# AdelinoR2B.net
KiCad netlist of a schematic drawn in EAGLE
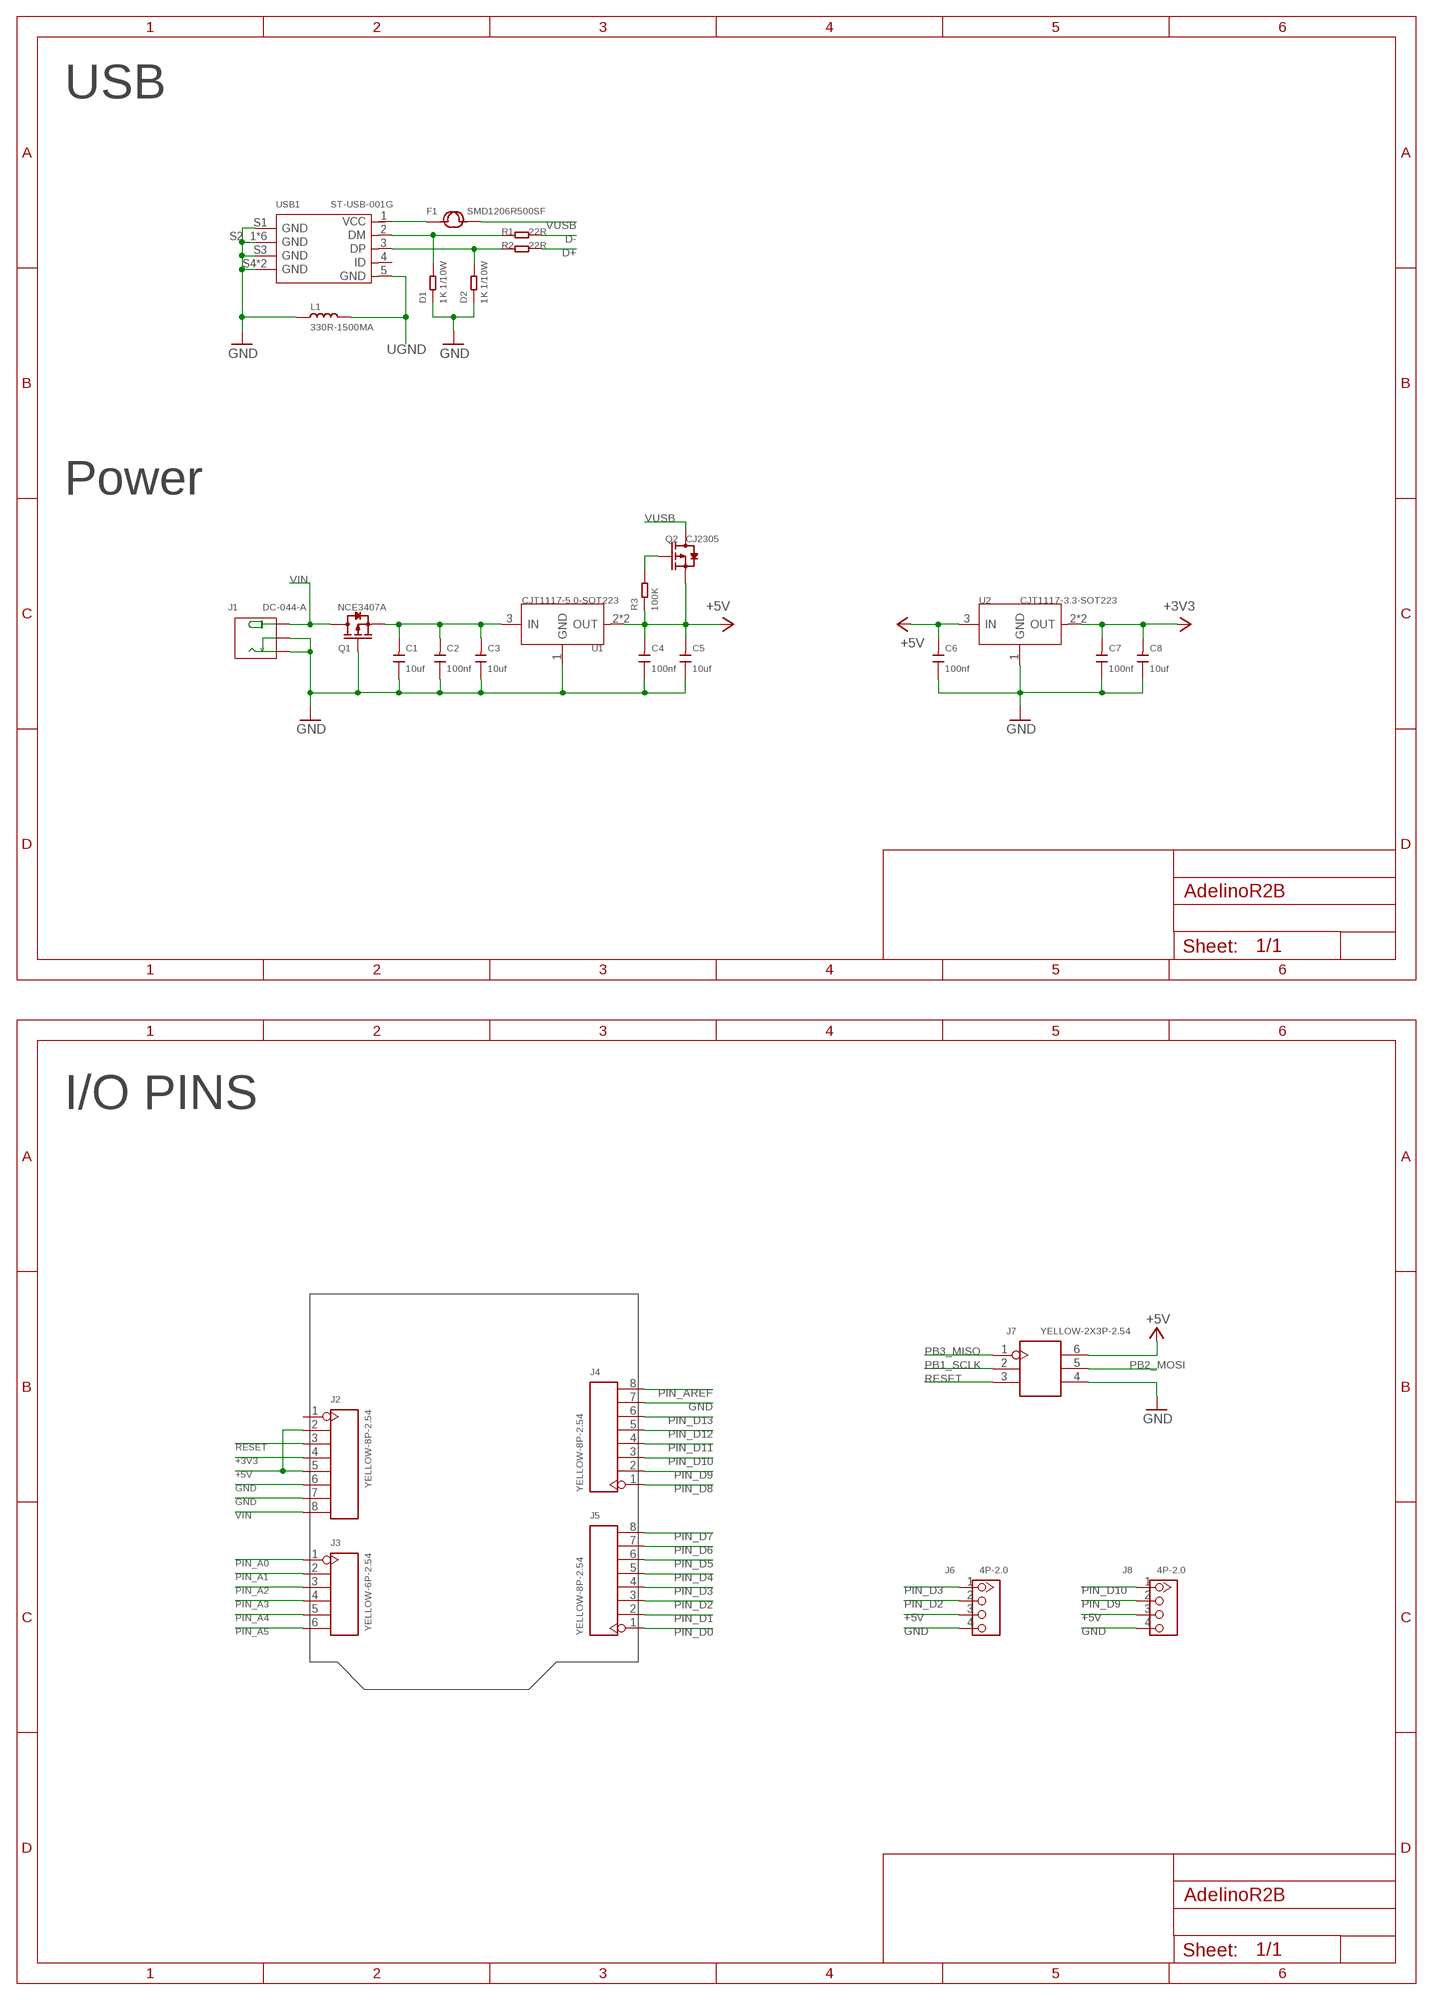
[diagram p0: schematic, sheet 1, part 1 of 2]
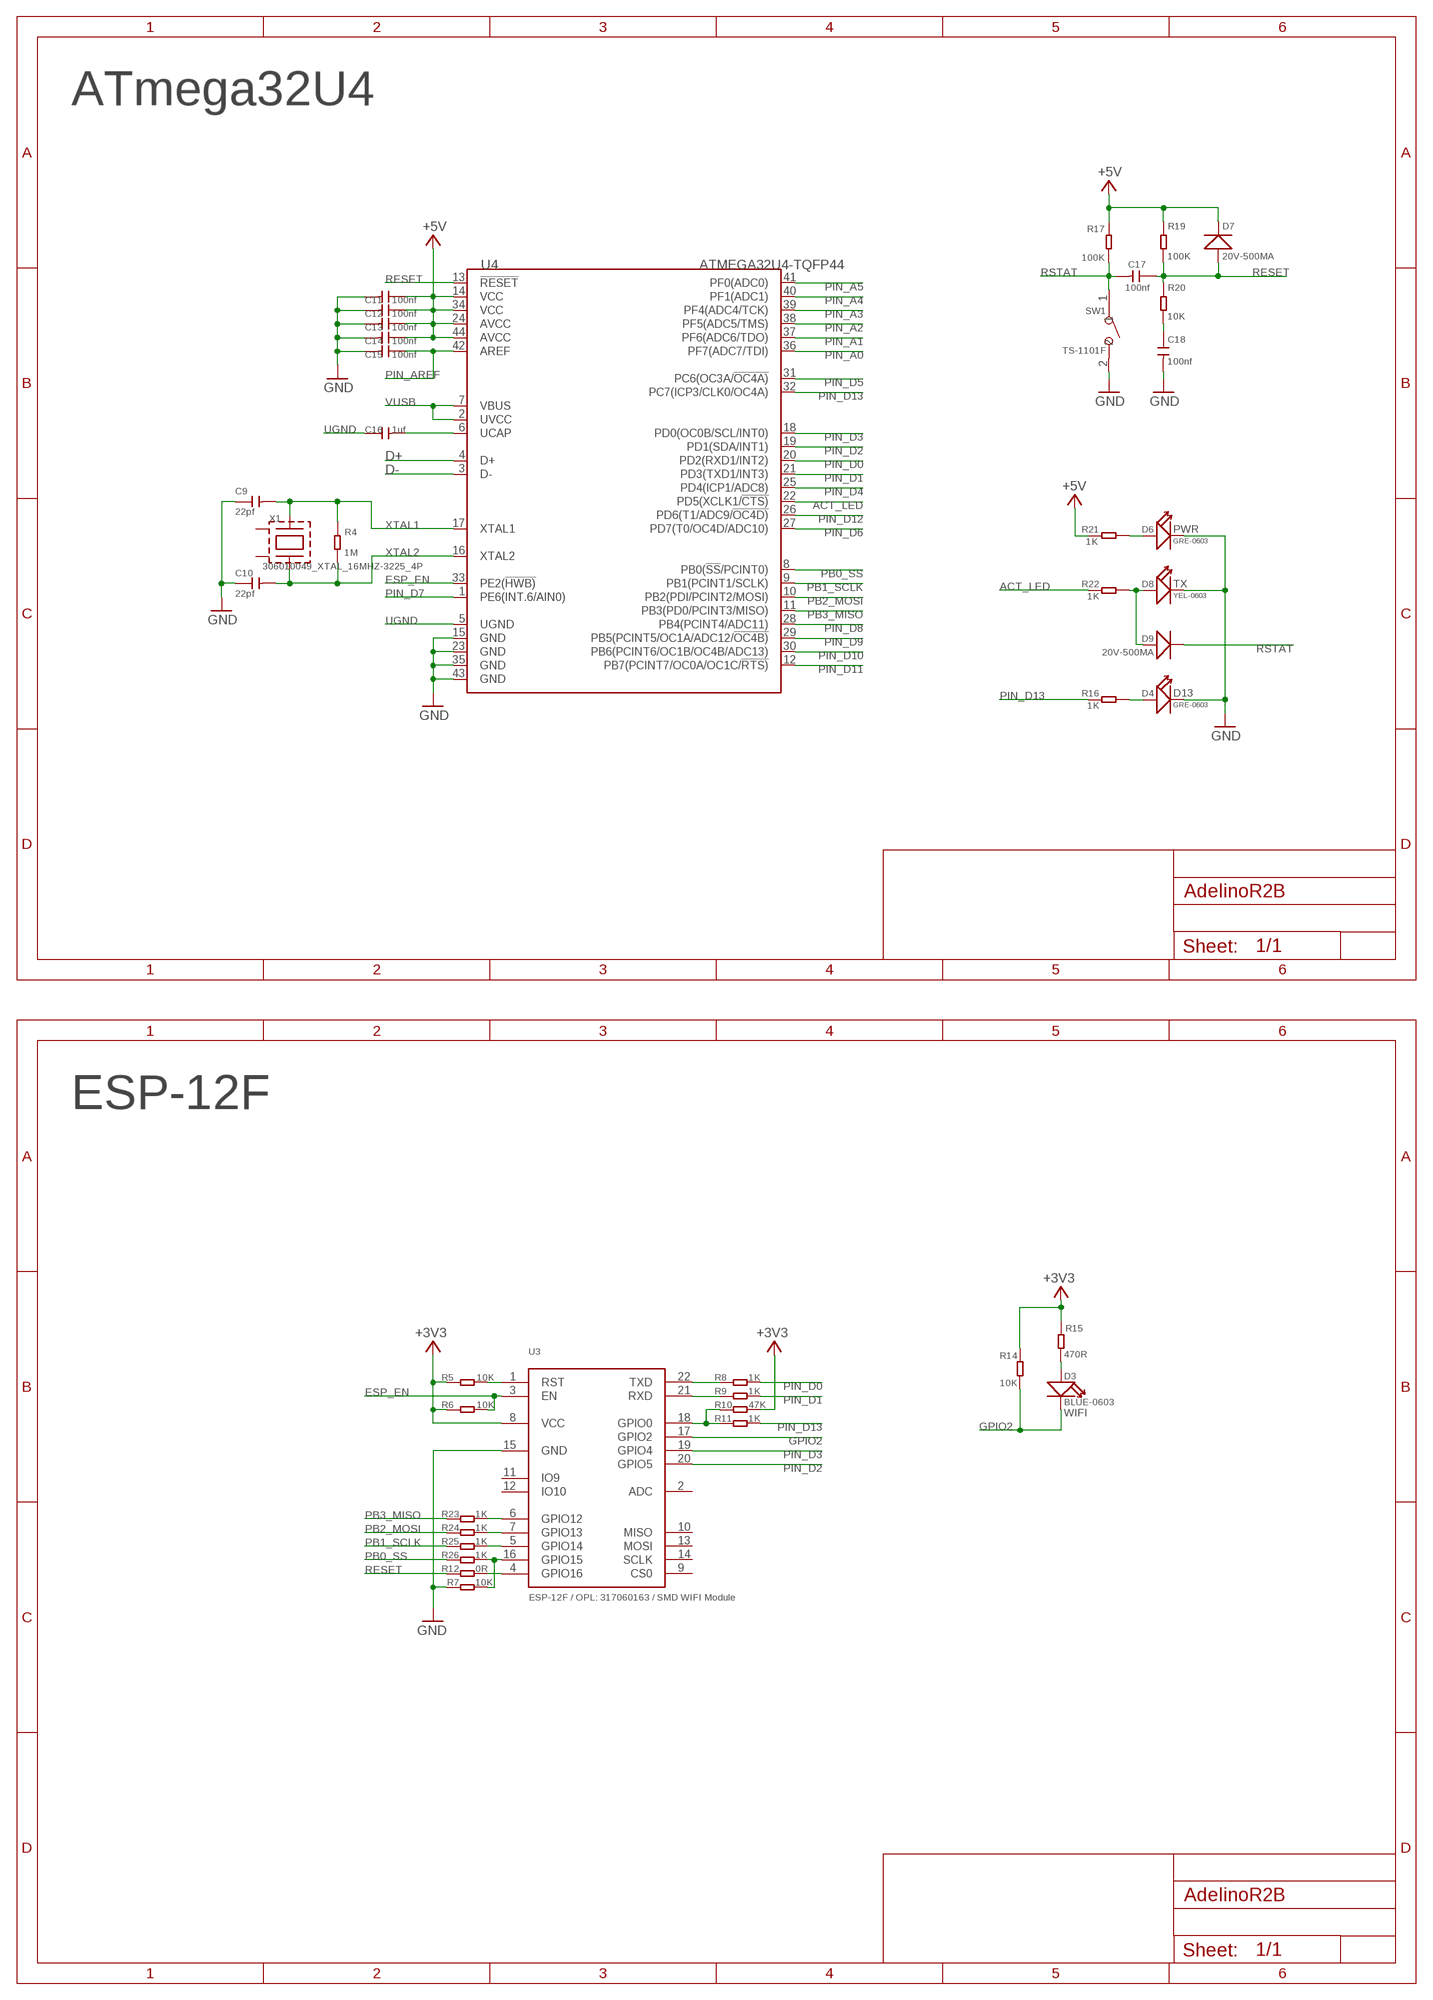
[diagram p1: schematic, sheet 1, part 2 of 2]

(export (version "E")
  (design (tool "Eeschema 10.0.6"))
  (components
    (comp (ref "C1")
      (value "10uf")
      (footprint "eagle-import:C0805")
      (fields (field (name "MPN") "CC0805KKX5R8BB106"))
      (libsource (lib "eagle-import") (part "CERAMIC-10UF-25V-10%-X5R(0805)"))
    )
    (comp (ref "C2")
      (value "100nf")
      (footprint "eagle-import:C0402")
      (fields (field (name "MPN") "CC0402KRX7R8BB104"))
      (libsource (lib "eagle-import") (part "CERAMIC-100NF-25V-10%-X7R(0402)"))
    )
    (comp (ref "C3")
      (value "10uf")
      (footprint "eagle-import:C0805")
      (fields (field (name "MPN") "CC0805KKX5R8BB106"))
      (libsource (lib "eagle-import") (part "CERAMIC-10UF-25V-10%-X5R(0805)"))
    )
    (comp (ref "C4")
      (value "100nf")
      (footprint "eagle-import:C0402")
      (fields (field (name "MPN") "CC0402KRX7R8BB104"))
      (libsource (lib "eagle-import") (part "CERAMIC-100NF-25V-10%-X7R(0402)"))
    )
    (comp (ref "C5")
      (value "10uf")
      (footprint "eagle-import:C0805")
      (fields (field (name "MPN") "CC0805KKX5R8BB106"))
      (libsource (lib "eagle-import") (part "CERAMIC-10UF-25V-10%-X5R(0805)"))
    )
    (comp (ref "C6")
      (value "100nf")
      (footprint "eagle-import:C0402")
      (fields (field (name "MPN") "CC0402KRX7R8BB104"))
      (libsource (lib "eagle-import") (part "CERAMIC-100NF-25V-10%-X7R(0402)"))
    )
    (comp (ref "C7")
      (value "100nf")
      (footprint "eagle-import:C0402")
      (fields (field (name "MPN") "CC0402KRX7R8BB104"))
      (libsource (lib "eagle-import") (part "CERAMIC-100NF-25V-10%-X7R(0402)"))
    )
    (comp (ref "C8")
      (value "10uf")
      (footprint "eagle-import:C0805")
      (fields (field (name "MPN") "CC0805KKX5R8BB106"))
      (libsource (lib "eagle-import") (part "CERAMIC-10UF-25V-10%-X5R(0805)"))
    )
    (comp (ref "C9")
      (value "22pf")
      (footprint "eagle-import:C0402")
      (fields (field (name "MPN") "CC0402JRNPO9BN220"))
      (libsource (lib "eagle-import") (part "CERAMIC-22PF-50V-5%-NPO(0402)"))
    )
    (comp (ref "C10")
      (value "22pf")
      (footprint "eagle-import:C0402")
      (fields (field (name "MPN") "CC0402JRNPO9BN220"))
      (libsource (lib "eagle-import") (part "CERAMIC-22PF-50V-5%-NPO(0402)"))
    )
    (comp (ref "C11")
      (value "100nf")
      (footprint "eagle-import:C0402")
      (fields (field (name "MPN") "CC0402KRX7R8BB104"))
      (libsource (lib "eagle-import") (part "CERAMIC-100NF-25V-10%-X7R(0402)"))
    )
    (comp (ref "C12")
      (value "100nf")
      (footprint "eagle-import:C0402")
      (fields (field (name "MPN") "CC0402KRX7R8BB104"))
      (libsource (lib "eagle-import") (part "CERAMIC-100NF-25V-10%-X7R(0402)"))
    )
    (comp (ref "C13")
      (value "100nf")
      (footprint "eagle-import:C0402")
      (fields (field (name "MPN") "CC0402KRX7R8BB104"))
      (libsource (lib "eagle-import") (part "CERAMIC-100NF-25V-10%-X7R(0402)"))
    )
    (comp (ref "C14")
      (value "100nf")
      (footprint "eagle-import:C0402")
      (fields (field (name "MPN") "CC0402KRX7R8BB104"))
      (libsource (lib "eagle-import") (part "CERAMIC-100NF-25V-10%-X7R(0402)"))
    )
    (comp (ref "C15")
      (value "100nf")
      (footprint "eagle-import:C0402")
      (fields (field (name "MPN") "CC0402KRX7R8BB104"))
      (libsource (lib "eagle-import") (part "CERAMIC-100NF-25V-10%-X7R(0402)"))
    )
    (comp (ref "C16")
      (value "1uf")
      (footprint "eagle-import:C0805")
      (fields (field (name "MPN") "CC0805KKX7R8BB105"))
      (libsource (lib "eagle-import") (part "CERAMIC-1UF-25V-10%-X7R(0805)"))
    )
    (comp (ref "C17")
      (value "100nf")
      (footprint "eagle-import:C0402")
      (fields (field (name "MPN") "CC0402KRX7R8BB104"))
      (libsource (lib "eagle-import") (part "CERAMIC-100NF-25V-10%-X7R(0402)"))
    )
    (comp (ref "C18")
      (value "100nf")
      (footprint "eagle-import:C0402")
      (fields (field (name "MPN") "CC0402KRX7R8BB104"))
      (libsource (lib "eagle-import") (part "CERAMIC-100NF-25V-10%-X7R(0402)"))
    )
    (comp (ref "D1")
      (value "1K 1/10W")
      (footprint "eagle-import:D0603")
      (fields (field (name "MPN") "RC0603JR-071KL"))
      (libsource (lib "eagle-import") (part "SMD-ESD-CG0603MLC-05E"))
    )
    (comp (ref "D2")
      (value "1K 1/10W")
      (footprint "eagle-import:D0603")
      (fields (field (name "MPN") "RC0603JR-071KL"))
      (libsource (lib "eagle-import") (part "SMD-ESD-CG0603MLC-05E"))
    )
    (comp (ref "D3")
      (value "BLUE-0603")
      (footprint "eagle-import:LED-0603")
      (fields (field (name "MPN") "19-217-BHC-ZL1M2RY-3T") (field (name "LABEL") "WIFI"))
      (libsource (lib "eagle-import") (part "SMD-LED-CLEAR-BLUE(0603)"))
    )
    (comp (ref "D4")
      (value "GRE-0603")
      (footprint "eagle-import:LED-0603")
      (fields (field (name "MPN") "19-217-G7C-AN1P2-3T") (field (name "LABEL") "D13"))
      (libsource (lib "eagle-import") (part "SMD-LED-CLEAR-GREEN(0603)"))
    )
    (comp (ref "D6")
      (value "GRE-0603")
      (footprint "eagle-import:LED-0603")
      (fields (field (name "MPN") "19-217-G7C-AN1P2-3T") (field (name "LABEL") "PWR"))
      (libsource (lib "eagle-import") (part "SMD-LED-CLEAR-GREEN(0603)"))
    )
    (comp (ref "D7")
      (value "20V-500MA")
      (footprint "eagle-import:SOD-123")
      (fields (field (name "MPN") "MBR0520LT1G"))
      (libsource (lib "eagle-import") (part "SMD-DIODE-SCHOTTKY-20V-500MA(SOD-123)P"))
    )
    (comp (ref "D8")
      (value "YEL-0603")
      (footprint "eagle-import:LED-0603")
      (fields (field (name "MPN") "19-217-Y5C-AM1N1VY-3T") (field (name "LABEL") "TX"))
      (libsource (lib "eagle-import") (part "SMD-LED-CLEAR-YELLOW(0603)"))
    )
    (comp (ref "D9")
      (value "20V-500MA")
      (footprint "eagle-import:SOD-123")
      (fields (field (name "MPN") "MBR0520LT1G"))
      (libsource (lib "eagle-import") (part "SMD-DIODE-SCHOTTKY-20V-500MA(SOD-123)P"))
    )
    (comp (ref "F1")
      (value "SMD1206R500SF")
      (footprint "eagle-import:F1206")
      (libsource (lib "eagle-import") (part "SMD-PPTC-500MA(1206)"))
    )
    (comp (ref "J1")
      (value "DC-044-A")
      (footprint "eagle-import:DCJ3P-11.6X9.6X7.0MM")
      (fields (field (name "MPN") "JACK-DC-044-A"))
      (libsource (lib "eagle-import") (part "JACK-DC-044-A"))
    )
    (comp (ref "J2")
      (value "YELLOW-8P-2.54")
      (footprint "eagle-import:H8-2.54")
      (fields (field (name "MPN") "F185-1108A1BSYC1"))
      (libsource (lib "eagle-import") (part "DIP-YELLOW-FEMALE-HEADER(8P-2.54)"))
    )
    (comp (ref "J3")
      (value "YELLOW-6P-2.54")
      (footprint "eagle-import:H6-2.54")
      (fields (field (name "MPN") "F185-1106A1BSYA3"))
      (libsource (lib "eagle-import") (part "DIP-YELLOW-FEMALE-HEADER-VERT(6P-2.54)"))
    )
    (comp (ref "J4")
      (value "YELLOW-8P-2.54")
      (footprint "eagle-import:H8-2.54")
      (fields (field (name "MPN") "F185-1108A1BSYC1"))
      (libsource (lib "eagle-import") (part "DIP-YELLOW-FEMALE-HEADER(8P-2.54)"))
    )
    (comp (ref "J5")
      (value "YELLOW-8P-2.54")
      (footprint "eagle-import:H8-2.54")
      (fields (field (name "MPN") "F185-1108A1BSYC1"))
      (libsource (lib "eagle-import") (part "DIP-YELLOW-FEMALE-HEADER(8P-2.54)"))
    )
    (comp (ref "J6")
      (value "4P-2.0")
      (footprint "eagle-import:HW4-2.0")
      (libsource (lib "eagle-import") (part "GROVE-CONNECTOR-DIP(4P-2.0)"))
    )
    (comp (ref "J7")
      (value "YELLOW-2X3P-2.54")
      (footprint "eagle-import:H2X3-2.54")
      (fields (field (name "MPN") "P125-1203A0BS116A2"))
      (libsource (lib "eagle-import") (part "DIP-YELLOW-MALE-HEADER-VERT(2X3P-2.54)"))
    )
    (comp (ref "J8")
      (value "4P-2.0")
      (footprint "eagle-import:HW4-2.0")
      (libsource (lib "eagle-import") (part "GROVE-CONNECTOR-DIP(4P-2.0)"))
    )
    (comp (ref "L1")
      (value "330R-1500MA")
      (footprint "eagle-import:L0805")
      (fields (field (name "MPN") "BLM21PG331SN1D"))
      (libsource (lib "eagle-import") (part "SMD-FERRITE-BEAD-330R-1500MA(0805)'0805'"))
    )
    (comp (ref "Q1")
      (value "NCE3407A")
      (footprint "eagle-import:SOT-23")
      (libsource (lib "eagle-import") (part "SMD-MOSFET-P-CH-VDC=30V-ID=4.3A-NCE3407A(SOT-23)"))
    )
    (comp (ref "Q2")
      (value "CJ2305")
      (footprint "eagle-import:SOT-23")
      (libsource (lib "eagle-import") (part "SMD-MOSFET-P-CH-8V-4.1A-CJ2305(SOT-23)"))
    )
    (comp (ref "R1")
      (value "22R")
      (footprint "eagle-import:R0402")
      (fields (field (name "MPN") "RC0402FR-0722RL"))
      (libsource (lib "eagle-import") (part "SMD-RES-22R-1%-1/16W(0402)"))
    )
    (comp (ref "R2")
      (value "22R")
      (footprint "eagle-import:R0402")
      (fields (field (name "MPN") "RC0402FR-0722RL"))
      (libsource (lib "eagle-import") (part "SMD-RES-22R-1%-1/16W(0402)"))
    )
    (comp (ref "R3")
      (value "100K")
      (footprint "eagle-import:R0402")
      (fields (field (name "MPN") "RC0402FR-07100KL"))
      (libsource (lib "eagle-import") (part "SMD-RES-100K-1%-1/16W(0402)"))
    )
    (comp (ref "R4")
      (value "1M")
      (footprint "eagle-import:R0402")
      (fields (field (name "MPN") "RC0402FR-071ML"))
      (libsource (lib "eagle-import") (part "SMD-RES-1M-1%-1/16W(0402)"))
    )
    (comp (ref "R5")
      (value "10K")
      (footprint "eagle-import:R0402")
      (fields (field (name "MPN") "RC0402FR-0710KL"))
      (libsource (lib "eagle-import") (part "SMD-RES-10K-1%-1/16W(0402)"))
    )
    (comp (ref "R6")
      (value "10K")
      (footprint "eagle-import:R0402")
      (fields (field (name "MPN") "RC0402FR-0710KL"))
      (libsource (lib "eagle-import") (part "SMD-RES-10K-1%-1/16W(0402)"))
    )
    (comp (ref "R7")
      (value "10K")
      (footprint "eagle-import:R0402")
      (fields (field (name "MPN") "RC0402FR-0710KL"))
      (libsource (lib "eagle-import") (part "SMD-RES-10K-1%-1/16W(0402)"))
    )
    (comp (ref "R8")
      (value "1K")
      (footprint "eagle-import:R0402")
      (fields (field (name "MPN") "RC0402JR-071KL"))
      (libsource (lib "eagle-import") (part "SMD-RES-1K-5%-1/16W(0402)"))
    )
    (comp (ref "R9")
      (value "1K")
      (footprint "eagle-import:R0402")
      (fields (field (name "MPN") "RC0402JR-071KL"))
      (libsource (lib "eagle-import") (part "SMD-RES-1K-5%-1/16W(0402)"))
    )
    (comp (ref "R10")
      (value "47K")
      (footprint "eagle-import:R0402")
      (fields (field (name "MPN") "RC0402JR-0747KL"))
      (libsource (lib "eagle-import") (part "SMD-RES-47K-5%-1/16W(0402)"))
    )
    (comp (ref "R11")
      (value "1K")
      (footprint "eagle-import:R0402")
      (fields (field (name "MPN") "RC0402JR-071KL"))
      (libsource (lib "eagle-import") (part "SMD-RES-1K-5%-1/16W(0402)"))
    )
    (comp (ref "R12")
      (value "0R")
      (footprint "eagle-import:R0402")
      (fields (field (name "MPN") "RC0402JR-070RL"))
      (libsource (lib "eagle-import") (part "SMD-RES-0R-5%-1/16W(0402)"))
    )
    (comp (ref "R14")
      (value "10K")
      (footprint "eagle-import:R0402")
      (fields (field (name "MPN") "RC0402FR-0710KL"))
      (libsource (lib "eagle-import") (part "SMD-RES-10K-1%-1/16W(0402)"))
    )
    (comp (ref "R15")
      (value "470R")
      (footprint "eagle-import:R0402")
      (fields (field (name "MPN") "RC0402JR-07470RL"))
      (libsource (lib "eagle-import") (part "SMD-RES-470R-5%-1/16W(0402)"))
    )
    (comp (ref "R16")
      (value "1K")
      (footprint "eagle-import:R0402")
      (fields (field (name "MPN") "RC0402JR-071KL"))
      (libsource (lib "eagle-import") (part "SMD-RES-1K-5%-1/16W(0402)"))
    )
    (comp (ref "R17")
      (value "100K")
      (footprint "eagle-import:R0402")
      (fields (field (name "MPN") "RC0402FR-07100KL"))
      (libsource (lib "eagle-import") (part "SMD-RES-100K-1%-1/16W(0402)"))
    )
    (comp (ref "R19")
      (value "100K")
      (footprint "eagle-import:R0402")
      (fields (field (name "MPN") "RC0402FR-07100KL"))
      (libsource (lib "eagle-import") (part "SMD-RES-100K-1%-1/16W(0402)"))
    )
    (comp (ref "R20")
      (value "10K")
      (footprint "eagle-import:R0402")
      (fields (field (name "MPN") "RC0402FR-0710KL"))
      (libsource (lib "eagle-import") (part "SMD-RES-10K-1%-1/16W(0402)"))
    )
    (comp (ref "R21")
      (value "1K")
      (footprint "eagle-import:R0402")
      (fields (field (name "MPN") "RC0402JR-071KL"))
      (libsource (lib "eagle-import") (part "SMD-RES-1K-5%-1/16W(0402)"))
    )
    (comp (ref "R22")
      (value "1K")
      (footprint "eagle-import:R0402")
      (fields (field (name "MPN") "RC0402JR-071KL"))
      (libsource (lib "eagle-import") (part "SMD-RES-1K-5%-1/16W(0402)"))
    )
    (comp (ref "R23")
      (value "1K")
      (footprint "eagle-import:R0402")
      (fields (field (name "MPN") "RC0402JR-071KL"))
      (libsource (lib "eagle-import") (part "SMD-RES-1K-5%-1/16W(0402)"))
    )
    (comp (ref "R24")
      (value "1K")
      (footprint "eagle-import:R0402")
      (fields (field (name "MPN") "RC0402JR-071KL"))
      (libsource (lib "eagle-import") (part "SMD-RES-1K-5%-1/16W(0402)"))
    )
    (comp (ref "R25")
      (value "1K")
      (footprint "eagle-import:R0402")
      (fields (field (name "MPN") "RC0402JR-071KL"))
      (libsource (lib "eagle-import") (part "SMD-RES-1K-5%-1/16W(0402)"))
    )
    (comp (ref "R26")
      (value "1K")
      (footprint "eagle-import:R0402")
      (fields (field (name "MPN") "RC0402JR-071KL"))
      (libsource (lib "eagle-import") (part "SMD-RES-1K-5%-1/16W(0402)"))
    )
    (comp (ref "SW1")
      (value "TS-1101F")
      (footprint "eagle-import:SW2-5.0-6.0X3.0X4.3MM")
      (libsource (lib "eagle-import") (part "DIP-BUTTON(2P-6.0X3.0X4.3MM)-TS-1101F"))
    )
    (comp (ref "U1")
      (value "CJT1117-5.0-SOT223")
      (footprint "eagle-import:SOT-223")
      (fields (field (name "MPN") "CJT1117-5.0"))
      (libsource (lib "eagle-import") (part "PMIC-CJT1117-5.0(SOT223)"))
    )
    (comp (ref "U2")
      (value "CJT1117-3.3-SOT223")
      (footprint "eagle-import:SOT-223")
      (fields (field (name "MPN") "CJT1117-3.3"))
      (libsource (lib "eagle-import") (part "PMIC-CJT1117-3.3(SOT223)"))
    )
    (comp (ref "U3")
      (value "ESP-12F / OPL: 317060163 / SMD WIFI Module")
      (footprint "eagle-import:ESP-12F")
      (libsource (lib "eagle-import") (part "ESP-12F"))
    )
    (comp (ref "U4")
      (value "ATMEGA32U4-TQFP44")
      (footprint "eagle-import:TQFP44-0.8-9.6X9.6MM")
      (fields (field (name "MPN") "ATMEGA32U4"))
      (libsource (lib "eagle-import") (part "MCU-ATMEGA32U4-AU(TQFP44)"))
    )
    (comp (ref "USB1")
      (value "ST-USB-001G")
      (footprint "eagle-import:MICRO-USB5+4P-SMD-0.65-B")
      (libsource (lib "eagle-import") (part "MICRO-USB-SMD-B-WITHOUT-POST-W/P(ST-USB-001G)"))
    )
    (comp (ref "X1")
      (value "306010049_XTAL_16MHZ-3225_4P")
      (footprint "eagle-import:X3225_4P")
      (libsource (lib "eagle-import") (part "306010049_XTAL_16MHZ-3225_4P"))
    )
  )
  (nets
    (net (code "1") (name "+3V3") (class "Default")
      (node (ref "C7") (pin "2") (pinfunction "2_2") (pintype "passive"))
      (node (ref "C8") (pin "2") (pinfunction "2_2") (pintype "passive"))
      (node (ref "J2") (pin "4") (pinfunction "4_4") (pintype "bidirectional"))
      (node (ref "R10") (pin "2") (pinfunction "2_2") (pintype "passive"))
      (node (ref "R14") (pin "2") (pinfunction "2_2") (pintype "passive"))
      (node (ref "R15") (pin "2") (pinfunction "2_2") (pintype "passive"))
      (node (ref "R5") (pin "1") (pinfunction "1_1") (pintype "passive"))
      (node (ref "R6") (pin "1") (pinfunction "1_1") (pintype "passive"))
      (node (ref "U2") (pin "2") (pinfunction "OUT_2") (pintype "bidirectional"))
      (node (ref "U2") (pin "TER") (pinfunction "OUT_TER") (pintype "bidirectional"))
      (node (ref "U3") (pin "8") (pinfunction "VCC_8") (pintype "bidirectional"))
    )
    (net (code "2") (name "+5V") (class "Default")
      (node (ref "C11") (pin "1") (pinfunction "1_1") (pintype "passive"))
      (node (ref "C12") (pin "1") (pinfunction "1_1") (pintype "passive"))
      (node (ref "C13") (pin "1") (pinfunction "1_1") (pintype "passive"))
      (node (ref "C14") (pin "1") (pinfunction "1_1") (pintype "passive"))
      (node (ref "C4") (pin "2") (pinfunction "2_2") (pintype "passive"))
      (node (ref "C5") (pin "2") (pinfunction "2_2") (pintype "passive"))
      (node (ref "C6") (pin "2") (pinfunction "2_2") (pintype "passive"))
      (node (ref "D7") (pin "-") (pinfunction "-_-") (pintype "passive"))
      (node (ref "J2") (pin "2") (pinfunction "2_2") (pintype "bidirectional"))
      (node (ref "J2") (pin "5") (pinfunction "5_5") (pintype "bidirectional"))
      (node (ref "J6") (pin "3") (pinfunction "3_3") (pintype "bidirectional"))
      (node (ref "J7") (pin "6") (pinfunction "6_6") (pintype "bidirectional"))
      (node (ref "J8") (pin "3") (pinfunction "3_3") (pintype "bidirectional"))
      (node (ref "Q2") (pin "2") (pinfunction "S_2") (pintype "passive"))
      (node (ref "R17") (pin "1") (pinfunction "1_1") (pintype "passive"))
      (node (ref "R19") (pin "2") (pinfunction "2_2") (pintype "passive"))
      (node (ref "R21") (pin "1") (pinfunction "1_1") (pintype "passive"))
      (node (ref "R3") (pin "1") (pinfunction "1_1") (pintype "passive"))
      (node (ref "U1") (pin "2") (pinfunction "OUT_2") (pintype "bidirectional"))
      (node (ref "U1") (pin "TER") (pinfunction "OUT_TER") (pintype "bidirectional"))
      (node (ref "U2") (pin "3") (pinfunction "IN_3") (pintype "bidirectional"))
      (node (ref "U4") (pin "14") (pinfunction "VCC_14") (pintype "bidirectional"))
      (node (ref "U4") (pin "24") (pinfunction "AVCC_24") (pintype "bidirectional"))
      (node (ref "U4") (pin "34") (pinfunction "VCC_34") (pintype "bidirectional"))
      (node (ref "U4") (pin "44") (pinfunction "AVCC_44") (pintype "bidirectional"))
    )
    (net (code "3") (name "/ACT_LED") (class "Default")
      (node (ref "R22") (pin "1") (pinfunction "1_1") (pintype "passive"))
      (node (ref "U4") (pin "22") (pinfunction "PD5(XCLK1/~{CTS})_22") (pintype "bidirectional"))
    )
    (net (code "4") (name "/D+") (class "Default")
      (node (ref "R2") (pin "2") (pinfunction "2_2") (pintype "passive"))
      (node (ref "U4") (pin "4") (pinfunction "D+_4") (pintype "bidirectional"))
    )
    (net (code "5") (name "/D-") (class "Default")
      (node (ref "R1") (pin "2") (pinfunction "2_2") (pintype "passive"))
      (node (ref "U4") (pin "3") (pinfunction "D-_3") (pintype "bidirectional"))
    )
    (net (code "6") (name "/ESP_EN") (class "Default")
      (node (ref "R6") (pin "2") (pinfunction "2_2") (pintype "passive"))
      (node (ref "U3") (pin "3") (pinfunction "EN_3") (pintype "bidirectional"))
      (node (ref "U4") (pin "33") (pinfunction "PE2(~{HWB})_33") (pintype "bidirectional"))
    )
    (net (code "7") (name "/GND1") (class "Default")
      (node (ref "X1") (pin "P$2") (pinfunction "GND1_P$2") (pintype "power_in"))
    )
    (net (code "8") (name "/GND2") (class "Default")
      (node (ref "X1") (pin "P$4") (pinfunction "GND2_P$4") (pintype "power_in"))
    )
    (net (code "9") (name "/GPIO2") (class "Default")
      (node (ref "D3") (pin "-") (pinfunction "-_-") (pintype "passive"))
      (node (ref "R14") (pin "1") (pinfunction "1_1") (pintype "passive"))
      (node (ref "U3") (pin "17") (pinfunction "GPIO2_17") (pintype "bidirectional"))
    )
    (net (code "10") (name "/PB0_SS") (class "Default")
      (node (ref "R26") (pin "1") (pinfunction "1_1") (pintype "passive"))
      (node (ref "U4") (pin "8") (pinfunction "PB0(~{SS}/PCINT0)_8") (pintype "bidirectional"))
    )
    (net (code "11") (name "/PB1_SCLK") (class "Default")
      (node (ref "J7") (pin "2") (pinfunction "2_2") (pintype "bidirectional"))
      (node (ref "R25") (pin "1") (pinfunction "1_1") (pintype "passive"))
      (node (ref "U4") (pin "9") (pinfunction "PB1(PCINT1/SCLK)_9") (pintype "bidirectional"))
    )
    (net (code "12") (name "/PB2_MOSI") (class "Default")
      (node (ref "J7") (pin "5") (pinfunction "5_5") (pintype "bidirectional"))
      (node (ref "R24") (pin "1") (pinfunction "1_1") (pintype "passive"))
      (node (ref "U4") (pin "10") (pinfunction "PB2(PDI/PCINT2/MOSI)_10") (pintype "bidirectional"))
    )
    (net (code "13") (name "/PB3_MISO") (class "Default")
      (node (ref "J7") (pin "1") (pinfunction "1_1") (pintype "bidirectional"))
      (node (ref "R23") (pin "1") (pinfunction "1_1") (pintype "passive"))
      (node (ref "U4") (pin "11") (pinfunction "PB3(PD0/PCINT3/MISO)_11") (pintype "bidirectional"))
    )
    (net (code "14") (name "/PIN_A0") (class "Default")
      (node (ref "J3") (pin "1") (pinfunction "1_1") (pintype "bidirectional"))
      (node (ref "U4") (pin "36") (pinfunction "PF7(ADC7/TDI)_36") (pintype "bidirectional"))
    )
    (net (code "15") (name "/PIN_A1") (class "Default")
      (node (ref "J3") (pin "2") (pinfunction "2_2") (pintype "bidirectional"))
      (node (ref "U4") (pin "37") (pinfunction "PF6(ADC6/TDO)_37") (pintype "bidirectional"))
    )
    (net (code "16") (name "/PIN_A2") (class "Default")
      (node (ref "J3") (pin "3") (pinfunction "3_3") (pintype "bidirectional"))
      (node (ref "U4") (pin "38") (pinfunction "PF5(ADC5/TMS)_38") (pintype "bidirectional"))
    )
    (net (code "17") (name "/PIN_A3") (class "Default")
      (node (ref "J3") (pin "4") (pinfunction "4_4") (pintype "bidirectional"))
      (node (ref "U4") (pin "39") (pinfunction "PF4(ADC4/TCK)_39") (pintype "bidirectional"))
    )
    (net (code "18") (name "/PIN_A4") (class "Default")
      (node (ref "J3") (pin "5") (pinfunction "5_5") (pintype "bidirectional"))
      (node (ref "U4") (pin "40") (pinfunction "PF1(ADC1)_40") (pintype "bidirectional"))
    )
    (net (code "19") (name "/PIN_A5") (class "Default")
      (node (ref "J3") (pin "6") (pinfunction "6_6") (pintype "bidirectional"))
      (node (ref "U4") (pin "41") (pinfunction "PF0(ADC0)_41") (pintype "bidirectional"))
    )
    (net (code "20") (name "/PIN_AREF") (class "Default")
      (node (ref "C15") (pin "1") (pinfunction "1_1") (pintype "passive"))
      (node (ref "J4") (pin "8") (pinfunction "8_8") (pintype "bidirectional"))
      (node (ref "U4") (pin "42") (pinfunction "AREF_42") (pintype "bidirectional"))
    )
    (net (code "21") (name "/PIN_D0") (class "Default")
      (node (ref "J5") (pin "1") (pinfunction "1_1") (pintype "bidirectional"))
      (node (ref "R8") (pin "2") (pinfunction "2_2") (pintype "passive"))
      (node (ref "U4") (pin "20") (pinfunction "PD2(RXD1/INT2)_20") (pintype "bidirectional"))
    )
    (net (code "22") (name "/PIN_D1") (class "Default")
      (node (ref "J5") (pin "2") (pinfunction "2_2") (pintype "bidirectional"))
      (node (ref "R9") (pin "2") (pinfunction "2_2") (pintype "passive"))
      (node (ref "U4") (pin "21") (pinfunction "PD3(TXD1/INT3)_21") (pintype "bidirectional"))
    )
    (net (code "23") (name "/PIN_D2") (class "Default")
      (node (ref "J5") (pin "3") (pinfunction "3_3") (pintype "bidirectional"))
      (node (ref "J6") (pin "2") (pinfunction "2_2") (pintype "bidirectional"))
      (node (ref "U3") (pin "20") (pinfunction "GPIO5_20") (pintype "bidirectional"))
      (node (ref "U4") (pin "19") (pinfunction "PD1(SDA/INT1)_19") (pintype "bidirectional"))
    )
    (net (code "24") (name "/PIN_D3") (class "Default")
      (node (ref "J5") (pin "4") (pinfunction "4_4") (pintype "bidirectional"))
      (node (ref "J6") (pin "1") (pinfunction "1_1") (pintype "bidirectional"))
      (node (ref "U3") (pin "19") (pinfunction "GPIO4_19") (pintype "bidirectional"))
      (node (ref "U4") (pin "18") (pinfunction "PD0(OC0B/SCL/INT0)_18") (pintype "bidirectional"))
    )
    (net (code "25") (name "/PIN_D4") (class "Default")
      (node (ref "J5") (pin "5") (pinfunction "5_5") (pintype "bidirectional"))
      (node (ref "U4") (pin "25") (pinfunction "PD4(ICP1/ADC8)_25") (pintype "bidirectional"))
    )
    (net (code "26") (name "/PIN_D5") (class "Default")
      (node (ref "J5") (pin "6") (pinfunction "6_6") (pintype "bidirectional"))
      (node (ref "U4") (pin "31") (pinfunction "PC6(OC3A/~{OC4A})_31") (pintype "bidirectional"))
    )
    (net (code "27") (name "/PIN_D6") (class "Default")
      (node (ref "J5") (pin "7") (pinfunction "7_7") (pintype "bidirectional"))
      (node (ref "U4") (pin "27") (pinfunction "PD7(T0/OC4D/ADC10)_27") (pintype "bidirectional"))
    )
    (net (code "28") (name "/PIN_D7") (class "Default")
      (node (ref "J5") (pin "8") (pinfunction "8_8") (pintype "bidirectional"))
      (node (ref "U4") (pin "1") (pinfunction "PE6(INT.6/AIN0)_1") (pintype "bidirectional"))
    )
    (net (code "29") (name "/PIN_D8") (class "Default")
      (node (ref "J4") (pin "1") (pinfunction "1_1") (pintype "bidirectional"))
      (node (ref "U4") (pin "28") (pinfunction "PB4(PCINT4/ADC11)_28") (pintype "bidirectional"))
    )
    (net (code "30") (name "/PIN_D9") (class "Default")
      (node (ref "J4") (pin "2") (pinfunction "2_2") (pintype "bidirectional"))
      (node (ref "J8") (pin "2") (pinfunction "2_2") (pintype "bidirectional"))
      (node (ref "U4") (pin "29") (pinfunction "PB5(PCINT5/OC1A/ADC12/~{OC4B})_29") (pintype "bidirectional"))
    )
    (net (code "31") (name "/PIN_D10") (class "Default")
      (node (ref "J4") (pin "3") (pinfunction "3_3") (pintype "bidirectional"))
      (node (ref "J8") (pin "1") (pinfunction "1_1") (pintype "bidirectional"))
      (node (ref "U4") (pin "30") (pinfunction "PB6(PCINT6/OC1B/OC4B/ADC13)_30") (pintype "bidirectional"))
    )
    (net (code "32") (name "/PIN_D11") (class "Default")
      (node (ref "J4") (pin "4") (pinfunction "4_4") (pintype "bidirectional"))
      (node (ref "U4") (pin "12") (pinfunction "PB7(PCINT7/OC0A/OC1C/~{RTS})_12") (pintype "bidirectional"))
    )
    (net (code "33") (name "/PIN_D12") (class "Default")
      (node (ref "J4") (pin "5") (pinfunction "5_5") (pintype "bidirectional"))
      (node (ref "U4") (pin "26") (pinfunction "PD6(T1/ADC9/~{OC4D})_26") (pintype "bidirectional"))
    )
    (net (code "34") (name "/PIN_D13") (class "Default")
      (node (ref "J4") (pin "6") (pinfunction "6_6") (pintype "bidirectional"))
      (node (ref "R11") (pin "2") (pinfunction "2_2") (pintype "passive"))
      (node (ref "R16") (pin "1") (pinfunction "1_1") (pintype "passive"))
      (node (ref "U4") (pin "32") (pinfunction "PC7(ICP3/CLK0/OC4A)_32") (pintype "bidirectional"))
    )
    (net (code "35") (name "/RESET") (class "Default")
      (node (ref "C17") (pin "1") (pinfunction "1_1") (pintype "passive"))
      (node (ref "D7") (pin "+") (pinfunction "+_+") (pintype "passive"))
      (node (ref "J2") (pin "3") (pinfunction "3_3") (pintype "bidirectional"))
      (node (ref "J7") (pin "3") (pinfunction "3_3") (pintype "bidirectional"))
      (node (ref "R12") (pin "1") (pinfunction "1_1") (pintype "passive"))
      (node (ref "R19") (pin "1") (pinfunction "1_1") (pintype "passive"))
      (node (ref "R20") (pin "1") (pinfunction "1_1") (pintype "passive"))
      (node (ref "U4") (pin "13") (pinfunction "~{RESET}_13") (pintype "bidirectional"))
    )
    (net (code "36") (name "/RSTAT") (class "Default")
      (node (ref "C17") (pin "2") (pinfunction "2_2") (pintype "passive"))
      (node (ref "D9") (pin "-") (pinfunction "-_-") (pintype "passive"))
      (node (ref "R17") (pin "2") (pinfunction "2_2") (pintype "passive"))
      (node (ref "SW1") (pin "1") (pinfunction "1_1") (pintype "bidirectional"))
    )
    (net (code "37") (name "/UGND") (class "Default")
      (node (ref "C16") (pin "1") (pinfunction "1_1") (pintype "passive"))
      (node (ref "L1") (pin "2") (pinfunction "2_2") (pintype "passive"))
      (node (ref "U4") (pin "5") (pinfunction "UGND_5") (pintype "bidirectional"))
      (node (ref "USB1") (pin "5") (pinfunction "GND_5") (pintype "bidirectional"))
    )
    (net (code "38") (name "/VIN") (class "Default")
      (node (ref "J1") (pin "VCC1") (pinfunction "+_VCC1") (pintype "bidirectional"))
      (node (ref "J1") (pin "VCC2") (pinfunction "+_VCC2") (pintype "bidirectional"))
      (node (ref "J1") (pin "VCC3") (pinfunction "+_VCC3") (pintype "bidirectional"))
      (node (ref "J1") (pin "VCC4") (pinfunction "+_VCC4") (pintype "bidirectional"))
      (node (ref "J2") (pin "8") (pinfunction "8_8") (pintype "bidirectional"))
      (node (ref "Q1") (pin "3") (pinfunction "D_3") (pintype "passive"))
    )
    (net (code "39") (name "/VUSB") (class "Default")
      (node (ref "F1") (pin "2") (pinfunction "2_2") (pintype "bidirectional"))
      (node (ref "Q2") (pin "3") (pinfunction "D_3") (pintype "passive"))
      (node (ref "U4") (pin "2") (pinfunction "UVCC_2") (pintype "bidirectional"))
      (node (ref "U4") (pin "7") (pinfunction "VBUS_7") (pintype "bidirectional"))
    )
    (net (code "40") (name "/XTAL1") (class "Default")
      (node (ref "C9") (pin "2") (pinfunction "2_2") (pintype "passive"))
      (node (ref "R4") (pin "2") (pinfunction "2_2") (pintype "passive"))
      (node (ref "U4") (pin "17") (pinfunction "XTAL1_17") (pintype "bidirectional"))
      (node (ref "X1") (pin "P$1") (pinfunction "P$1_P$1") (pintype "passive"))
    )
    (net (code "41") (name "/XTAL2") (class "Default")
      (node (ref "C10") (pin "2") (pinfunction "2_2") (pintype "passive"))
      (node (ref "R4") (pin "1") (pinfunction "1_1") (pintype "passive"))
      (node (ref "U4") (pin "16") (pinfunction "XTAL2_16") (pintype "bidirectional"))
      (node (ref "X1") (pin "P$3") (pinfunction "P$2_P$3") (pintype "passive"))
    )
    (net (code "42") (name "GND") (class "Default")
      (node (ref "C1") (pin "1") (pinfunction "1_1") (pintype "passive"))
      (node (ref "C10") (pin "1") (pinfunction "1_1") (pintype "passive"))
      (node (ref "C11") (pin "2") (pinfunction "2_2") (pintype "passive"))
      (node (ref "C12") (pin "2") (pinfunction "2_2") (pintype "passive"))
      (node (ref "C13") (pin "2") (pinfunction "2_2") (pintype "passive"))
      (node (ref "C14") (pin "2") (pinfunction "2_2") (pintype "passive"))
      (node (ref "C15") (pin "2") (pinfunction "2_2") (pintype "passive"))
      (node (ref "C18") (pin "2") (pinfunction "2_2") (pintype "passive"))
      (node (ref "C2") (pin "1") (pinfunction "1_1") (pintype "passive"))
      (node (ref "C3") (pin "1") (pinfunction "1_1") (pintype "passive"))
      (node (ref "C4") (pin "1") (pinfunction "1_1") (pintype "passive"))
      (node (ref "C5") (pin "1") (pinfunction "1_1") (pintype "passive"))
      (node (ref "C6") (pin "1") (pinfunction "1_1") (pintype "passive"))
      (node (ref "C7") (pin "1") (pinfunction "1_1") (pintype "passive"))
      (node (ref "C8") (pin "1") (pinfunction "1_1") (pintype "passive"))
      (node (ref "C9") (pin "1") (pinfunction "1_1") (pintype "passive"))
      (node (ref "D1") (pin "1") (pinfunction "1_1") (pintype "passive"))
      (node (ref "D2") (pin "1") (pinfunction "1_1") (pintype "passive"))
      (node (ref "D4") (pin "-") (pinfunction "-_-") (pintype "passive"))
      (node (ref "D6") (pin "-") (pinfunction "-_-") (pintype "passive"))
      (node (ref "D8") (pin "-") (pinfunction "-_-") (pintype "passive"))
      (node (ref "J1") (pin "CDN1") (pinfunction "CDN_CDN1") (pintype "bidirectional"))
      (node (ref "J1") (pin "CDN2") (pinfunction "CDN_CDN2") (pintype "bidirectional"))
      (node (ref "J1") (pin "CDN3") (pinfunction "CDN_CDN3") (pintype "bidirectional"))
      (node (ref "J1") (pin "CDN4") (pinfunction "CDN_CDN4") (pintype "bidirectional"))
      (node (ref "J1") (pin "GND1") (pinfunction "-_GND1") (pintype "bidirectional"))
      (node (ref "J1") (pin "GND2") (pinfunction "-_GND2") (pintype "bidirectional"))
      (node (ref "J1") (pin "GND3") (pinfunction "-_GND3") (pintype "bidirectional"))
      (node (ref "J1") (pin "GND4") (pinfunction "-_GND4") (pintype "bidirectional"))
      (node (ref "J2") (pin "6") (pinfunction "6_6") (pintype "bidirectional"))
      (node (ref "J2") (pin "7") (pinfunction "7_7") (pintype "bidirectional"))
      (node (ref "J4") (pin "7") (pinfunction "7_7") (pintype "bidirectional"))
      (node (ref "J6") (pin "4") (pinfunction "4_4") (pintype "bidirectional"))
      (node (ref "J7") (pin "4") (pinfunction "4_4") (pintype "bidirectional"))
      (node (ref "J8") (pin "4") (pinfunction "4_4") (pintype "bidirectional"))
      (node (ref "L1") (pin "1") (pinfunction "1_1") (pintype "passive"))
      (node (ref "Q1") (pin "1") (pinfunction "G_1") (pintype "passive"))
      (node (ref "R7") (pin "1") (pinfunction "1_1") (pintype "passive"))
      (node (ref "SW1") (pin "2") (pinfunction "2_2") (pintype "bidirectional"))
      (node (ref "U1") (pin "1") (pinfunction "GND_1") (pintype "bidirectional"))
      (node (ref "U2") (pin "1") (pinfunction "GND_1") (pintype "bidirectional"))
      (node (ref "U3") (pin "15") (pinfunction "GND_15") (pintype "bidirectional"))
      (node (ref "U4") (pin "15") (pinfunction "GND_15") (pintype "bidirectional"))
      (node (ref "U4") (pin "23") (pinfunction "GND_23") (pintype "bidirectional"))
      (node (ref "U4") (pin "35") (pinfunction "GND_35") (pintype "bidirectional"))
      (node (ref "U4") (pin "43") (pinfunction "GND_43") (pintype "bidirectional"))
      (node (ref "USB1") (pin "S1") (pinfunction "GND_S1") (pintype "bidirectional"))
      (node (ref "USB1") (pin "S2_1") (pinfunction "GND_S2_1") (pintype "bidirectional"))
      (node (ref "USB1") (pin "S2_2") (pinfunction "GND_S2_2") (pintype "bidirectional"))
      (node (ref "USB1") (pin "S2_3") (pinfunction "GND_S2_3") (pintype "bidirectional"))
      (node (ref "USB1") (pin "S3") (pinfunction "GND_S3") (pintype "bidirectional"))
      (node (ref "USB1") (pin "S4") (pinfunction "GND_S4") (pintype "bidirectional"))
      (node (ref "USB1") (pin "S5_1") (pinfunction "GND_S5_1") (pintype "bidirectional"))
      (node (ref "USB1") (pin "S5_2") (pinfunction "GND_S5_2") (pintype "bidirectional"))
      (node (ref "USB1") (pin "S5_3") (pinfunction "GND_S5_3") (pintype "bidirectional"))
      (node (ref "USB1") (pin "S6") (pinfunction "GND_S6") (pintype "bidirectional"))
    )
    (net (code "43") (name "Net-(C18-Pad1)") (class "Default")
      (node (ref "C18") (pin "1") (pinfunction "1_1") (pintype "passive"))
      (node (ref "R20") (pin "2") (pinfunction "2_2") (pintype "passive"))
    )
    (net (code "44") (name "Net-(D3-Pad+)") (class "Default")
      (node (ref "D3") (pin "+") (pinfunction "+_+") (pintype "passive"))
      (node (ref "R15") (pin "1") (pinfunction "1_1") (pintype "passive"))
    )
    (net (code "45") (name "Net-(D4-Pad+)") (class "Default")
      (node (ref "D4") (pin "+") (pinfunction "+_+") (pintype "passive"))
      (node (ref "R16") (pin "2") (pinfunction "2_2") (pintype "passive"))
    )
    (net (code "46") (name "Net-(D6-Pad+)") (class "Default")
      (node (ref "D6") (pin "+") (pinfunction "+_+") (pintype "passive"))
      (node (ref "R21") (pin "2") (pinfunction "2_2") (pintype "passive"))
    )
    (net (code "47") (name "Net-(D8-Pad+)") (class "Default")
      (node (ref "D8") (pin "+") (pinfunction "+_+") (pintype "passive"))
      (node (ref "D9") (pin "+") (pinfunction "+_+") (pintype "passive"))
      (node (ref "R22") (pin "2") (pinfunction "2_2") (pintype "passive"))
    )
    (net (code "48") (name "Net-(Q1-S)") (class "Default")
      (node (ref "C1") (pin "2") (pinfunction "2_2") (pintype "passive"))
      (node (ref "C2") (pin "2") (pinfunction "2_2") (pintype "passive"))
      (node (ref "C3") (pin "2") (pinfunction "2_2") (pintype "passive"))
      (node (ref "Q1") (pin "2") (pinfunction "S_2") (pintype "passive"))
      (node (ref "U1") (pin "3") (pinfunction "IN_3") (pintype "bidirectional"))
    )
    (net (code "49") (name "Net-(Q2-G)") (class "Default")
      (node (ref "Q2") (pin "1") (pinfunction "G_1") (pintype "passive"))
      (node (ref "R3") (pin "2") (pinfunction "2_2") (pintype "passive"))
    )
    (net (code "50") (name "Net-(U3-GPIO0)") (class "Default")
      (node (ref "R10") (pin "1") (pinfunction "1_1") (pintype "passive"))
      (node (ref "R11") (pin "1") (pinfunction "1_1") (pintype "passive"))
      (node (ref "U3") (pin "18") (pinfunction "GPIO0_18") (pintype "bidirectional"))
    )
    (net (code "51") (name "Net-(U3-GPIO12)") (class "Default")
      (node (ref "R23") (pin "2") (pinfunction "2_2") (pintype "passive"))
      (node (ref "U3") (pin "6") (pinfunction "GPIO12_6") (pintype "bidirectional"))
    )
    (net (code "52") (name "Net-(U3-GPIO13)") (class "Default")
      (node (ref "R24") (pin "2") (pinfunction "2_2") (pintype "passive"))
      (node (ref "U3") (pin "7") (pinfunction "GPIO13_7") (pintype "bidirectional"))
    )
    (net (code "53") (name "Net-(U3-GPIO14)") (class "Default")
      (node (ref "R25") (pin "2") (pinfunction "2_2") (pintype "passive"))
      (node (ref "U3") (pin "5") (pinfunction "GPIO14_5") (pintype "bidirectional"))
    )
    (net (code "54") (name "Net-(U3-GPIO15)") (class "Default")
      (node (ref "R26") (pin "2") (pinfunction "2_2") (pintype "passive"))
      (node (ref "R7") (pin "2") (pinfunction "2_2") (pintype "passive"))
      (node (ref "U3") (pin "16") (pinfunction "GPIO15_16") (pintype "bidirectional"))
    )
    (net (code "55") (name "Net-(U3-GPIO16)") (class "Default")
      (node (ref "R12") (pin "2") (pinfunction "2_2") (pintype "passive"))
      (node (ref "U3") (pin "4") (pinfunction "GPIO16_4") (pintype "bidirectional"))
    )
    (net (code "56") (name "Net-(U3-RST)") (class "Default")
      (node (ref "R5") (pin "2") (pinfunction "2_2") (pintype "passive"))
      (node (ref "U3") (pin "1") (pinfunction "RST_1") (pintype "bidirectional"))
    )
    (net (code "57") (name "Net-(U3-RXD)") (class "Default")
      (node (ref "R9") (pin "1") (pinfunction "1_1") (pintype "passive"))
      (node (ref "U3") (pin "21") (pinfunction "RXD_21") (pintype "bidirectional"))
    )
    (net (code "58") (name "Net-(U3-TXD)") (class "Default")
      (node (ref "R8") (pin "1") (pinfunction "1_1") (pintype "passive"))
      (node (ref "U3") (pin "22") (pinfunction "TXD_22") (pintype "bidirectional"))
    )
    (net (code "59") (name "Net-(U4-UCAP)") (class "Default")
      (node (ref "C16") (pin "2") (pinfunction "2_2") (pintype "passive"))
      (node (ref "U4") (pin "6") (pinfunction "UCAP_6") (pintype "bidirectional"))
    )
    (net (code "60") (name "Net-(USB1-DM)") (class "Default")
      (node (ref "D1") (pin "2") (pinfunction "2_2") (pintype "passive"))
      (node (ref "R1") (pin "1") (pinfunction "1_1") (pintype "passive"))
      (node (ref "USB1") (pin "2") (pinfunction "DM_2") (pintype "bidirectional"))
    )
    (net (code "61") (name "Net-(USB1-DP)") (class "Default")
      (node (ref "D2") (pin "2") (pinfunction "2_2") (pintype "passive"))
      (node (ref "R2") (pin "1") (pinfunction "1_1") (pintype "passive"))
      (node (ref "USB1") (pin "3") (pinfunction "DP_3") (pintype "bidirectional"))
    )
    (net (code "62") (name "Net-(USB1-VCC)") (class "Default")
      (node (ref "F1") (pin "1") (pinfunction "1_1") (pintype "bidirectional"))
      (node (ref "USB1") (pin "1") (pinfunction "VCC_1") (pintype "bidirectional"))
    )
    (net (code "63") (name "unconnected-(J2-Pad1)") (class "Default")
      (node (ref "J2") (pin "1") (pinfunction "1_1") (pintype "bidirectional"))
    )
    (net (code "64") (name "unconnected-(U3-ADC-Pad2)") (class "Default")
      (node (ref "U3") (pin "2") (pinfunction "ADC_2") (pintype "bidirectional"))
    )
    (net (code "65") (name "unconnected-(U3-CS0-Pad9)") (class "Default")
      (node (ref "U3") (pin "9") (pinfunction "CS0_9") (pintype "bidirectional"))
    )
    (net (code "66") (name "unconnected-(U3-IO9-Pad11)") (class "Default")
      (node (ref "U3") (pin "11") (pinfunction "IO9_11") (pintype "bidirectional"))
    )
    (net (code "67") (name "unconnected-(U3-IO10-Pad12)") (class "Default")
      (node (ref "U3") (pin "12") (pinfunction "IO10_12") (pintype "bidirectional"))
    )
    (net (code "68") (name "unconnected-(U3-MISO-Pad10)") (class "Default")
      (node (ref "U3") (pin "10") (pinfunction "MISO_10") (pintype "bidirectional"))
    )
    (net (code "69") (name "unconnected-(U3-MOSI-Pad13)") (class "Default")
      (node (ref "U3") (pin "13") (pinfunction "MOSI_13") (pintype "bidirectional"))
    )
    (net (code "70") (name "unconnected-(U3-SCLK-Pad14)") (class "Default")
      (node (ref "U3") (pin "14") (pinfunction "SCLK_14") (pintype "bidirectional"))
    )
    (net (code "71") (name "unconnected-(USB1-ID-Pad4)") (class "Default")
      (node (ref "USB1") (pin "4") (pinfunction "ID_4") (pintype "bidirectional"))
    )
  )
)
